# stm32f103.net
KiCad netlist of a schematic drawn in Altium Designer
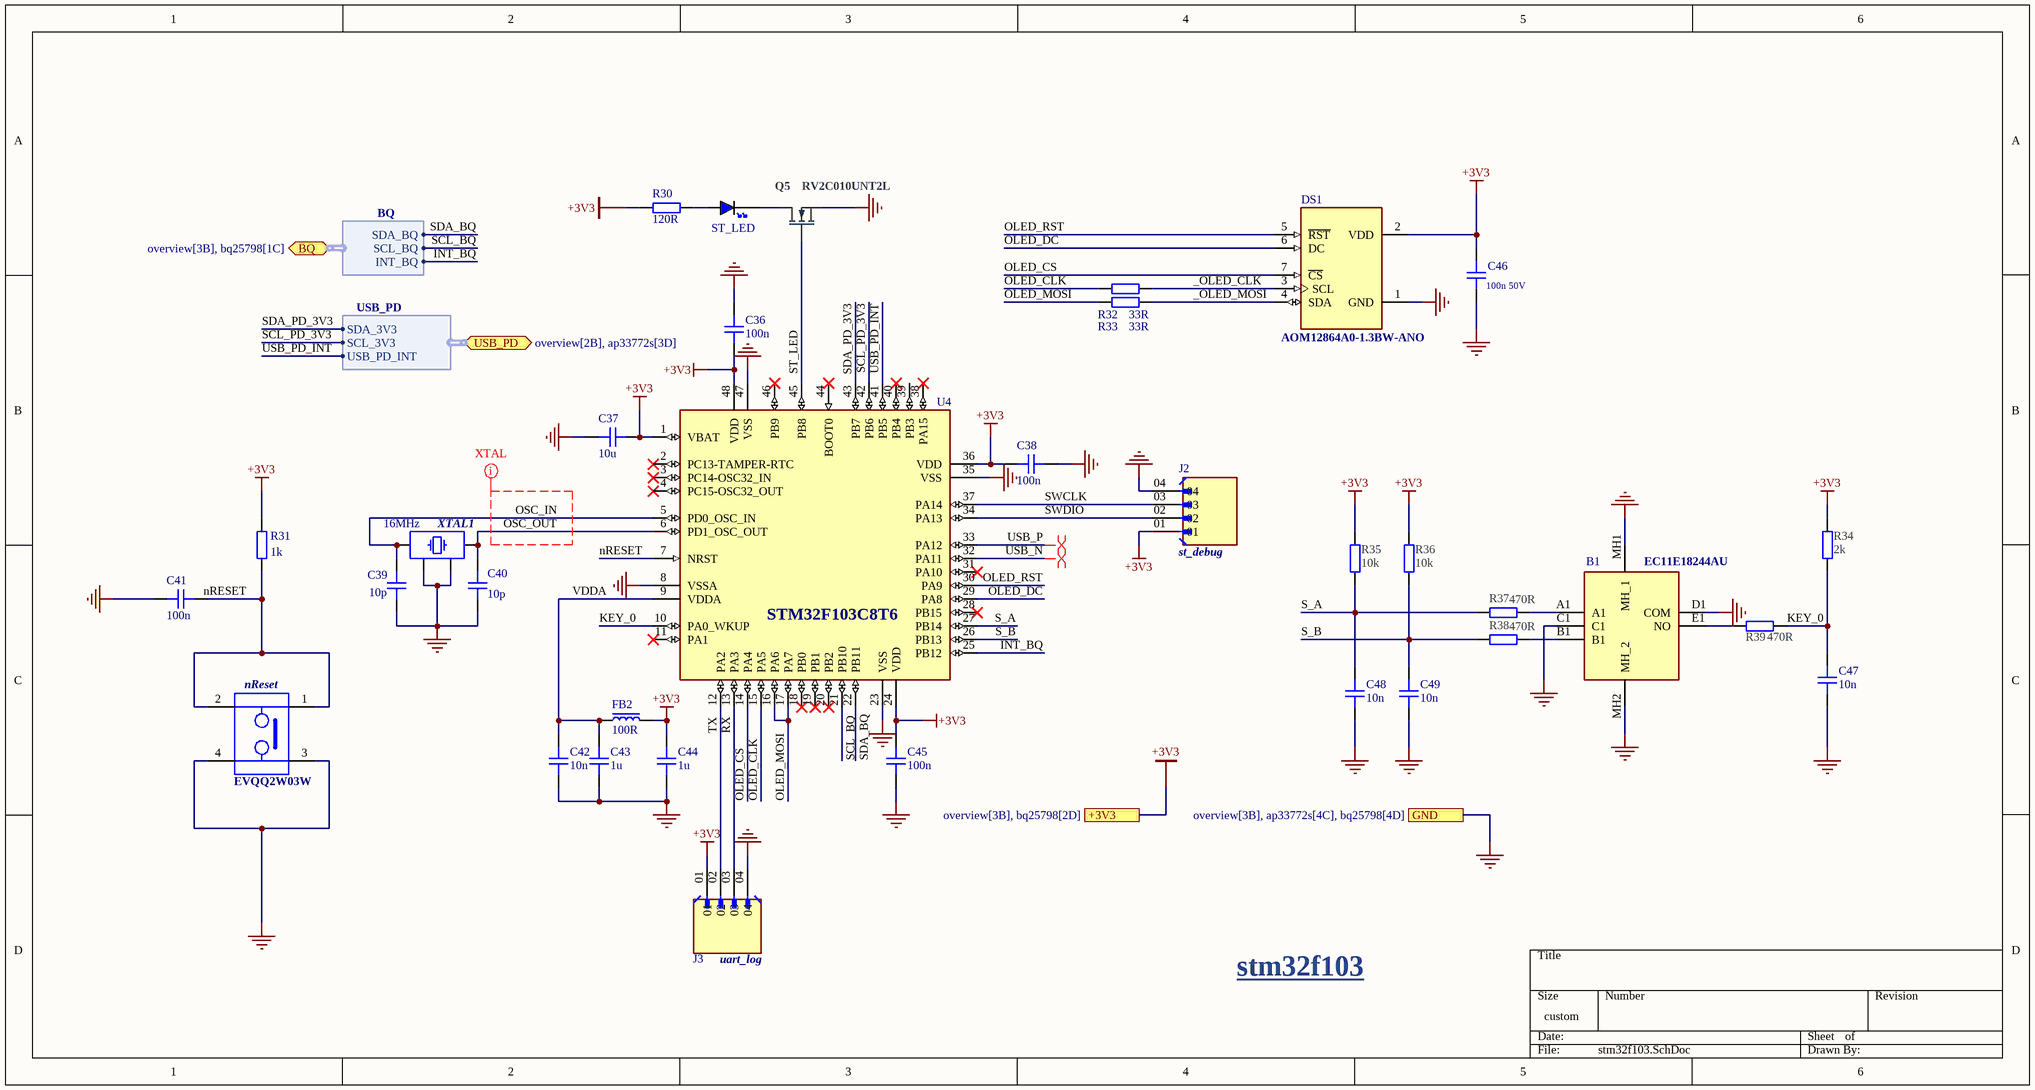
[diagram p0: stm32f103.SchDoc]

(export (version "E")
  (design (tool "Eeschema 10.0.6"))
  (components
    (comp (ref "B1")
      (value "EC11E18244AU")
      (footprint "EC11E18244AU")
      (fields (field (name "MOUSER PART NUMBER") "688-EC11E18244AU"))
      (libsource (lib "Sch_Lib") (part "EC11E18244AU"))
    )
    (comp (ref "C36")
      (value "100n")
      (footprint "CAP_0402")
      (description "Capacitor SMD 0402")
      (libsource (lib "Sch_Lib") (part "CAP_0402"))
    )
    (comp (ref "C37")
      (value "10u")
      (footprint "CAP_0402")
      (description "Capacitor SMD 0402")
      (libsource (lib "Sch_Lib") (part "CAP_0402"))
    )
    (comp (ref "C38")
      (value "100n")
      (footprint "CAP_0402")
      (description "Capacitor SMD 0402")
      (libsource (lib "Sch_Lib") (part "CAP_0402"))
    )
    (comp (ref "C39")
      (value "10p")
      (footprint "CAP_0402")
      (description "Capacitor SMD 0402")
      (libsource (lib "Schematic-Lib-PhilsLab") (part "CAP_0402"))
    )
    (comp (ref "C40")
      (value "10p")
      (footprint "CAP_0402")
      (description "Capacitor SMD 0402")
      (libsource (lib "Schematic-Lib-PhilsLab") (part "CAP_0402"))
    )
    (comp (ref "C41")
      (value "100n")
      (footprint "CAP_0603")
      (description "Capacitor SMD 0603")
      (libsource (lib "Sch_Lib") (part "CAP_0603"))
    )
    (comp (ref "C42")
      (value "10n")
      (footprint "CAP_0603")
      (description "Capacitor SMD 0603")
      (libsource (lib "Schematic-Lib-PhilsLab") (part "CAP_0603"))
    )
    (comp (ref "C43")
      (value "1u")
      (footprint "CAP_0603")
      (description "Capacitor SMD 0603")
      (libsource (lib "Schematic-Lib-PhilsLab") (part "CAP_0603"))
    )
    (comp (ref "C44")
      (value "1u")
      (footprint "CAP_0603")
      (description "Capacitor SMD 0603")
      (libsource (lib "Schematic-Lib-PhilsLab") (part "CAP_0603"))
    )
    (comp (ref "C45")
      (value "100n")
      (footprint "CAP_0402")
      (description "Capacitor SMD 0402")
      (libsource (lib "Sch_Lib") (part "CAP_0402"))
    )
    (comp (ref "C46")
      (value "100n 50V")
      (footprint "CAP_0603")
      (description "Capacitor SMD 0603")
      (libsource (lib "Sch_Lib") (part "CAP_0603"))
    )
    (comp (ref "C47")
      (value "10n")
      (footprint "CAP_0402")
      (description "Capacitor SMD 0402")
      (libsource (lib "Sch_Lib") (part "CAP_0402"))
    )
    (comp (ref "C48")
      (value "10n")
      (footprint "CAP_0402")
      (description "Capacitor SMD 0402")
      (libsource (lib "Sch_Lib") (part "CAP_0402"))
    )
    (comp (ref "C49")
      (value "10n")
      (footprint "CAP_0402")
      (description "Capacitor SMD 0402")
      (libsource (lib "Sch_Lib") (part "CAP_0402"))
    )
    (comp (ref "DS1")
      (value "AOM12864A0-1.3BW-ANO")
      (footprint "LCD_AOM12864A0-1.3BW-ANO")
      (description "Non-Touch Graphic LCD Display Module - Blue OLED SPI 1.3 (33.02mm) 128 x 64")
      (fields (field (name "MF") "Orient Display"))
      (libsource (lib "Sch_Lib") (part "AOM12864A0-1.3BW-ANO"))
    )
    (comp (ref "FB2")
      (value "100R")
      (footprint "FB_0603")
      (description "Ferrite Bead SMD 0603")
      (libsource (lib "Schematic-Lib-PhilsLab") (part "FB_0603"))
    )
    (comp (ref "J2")
      (value "st_debug")
      (footprint "SAMTEC_TSW-104-08-T-S-LL")
      (fields (field (name "MF") "Samtec") (field (name "MP") "TSW-104-08-T-S-LL"))
      (libsource (lib "Sch_Lib") (part "4PIN_TSW-104-08-T-S-LL"))
    )
    (comp (ref "J3")
      (value "uart_log")
      (footprint "SAMTEC_TSW-104-08-T-S-LL")
      (fields (field (name "MF") "Samtec") (field (name "MP") "TSW-104-08-T-S-LL"))
      (libsource (lib "") (part "4PIN_TSW-104-08-T-S-LL_1"))
    )
    (comp (ref "nReset")
      (value "EVQQ2W03W")
      (footprint "EVQQ2W03W")
      (description "White Push Plate Tactile Switch, SPST-NO 20 mA 3.1mm")
      (fields (field (name "MF") "Panasonic"))
      (libsource (lib "Sch_Lib") (part "EVQQ2W03W"))
    )
    (comp (ref "Q5")
      (value "RV2C010UNT2L")
      (footprint "DFN65P100X40-3L")
      (description "N-Channel MOSFET, 20V, 1A, 470mOhm, 400mW")
      (fields (field (name "MANUFACTURER") "Rohm Semiconductor") (field (name "AUTHOR") "rsk"))
      (libsource (lib "Sch_Lib") (part "RV2C010UNT2L"))
    )
    (comp (ref "R30")
      (value "120R")
      (footprint "RES_0603")
      (description "Resistor SMD 0603")
      (libsource (lib "Schematic-Lib-PhilsLab") (part "RES_0603"))
    )
    (comp (ref "R31")
      (value "1k")
      (footprint "RES_0603")
      (description "Resistor SMD 0603")
      (libsource (lib "Schematic-Lib-PhilsLab") (part "RES_0603"))
    )
    (comp (ref "R32")
      (value "33R")
      (footprint "RES_0603")
      (description "Resistor SMD 0603")
      (libsource (lib "Sch_Lib") (part "RES_0603"))
    )
    (comp (ref "R33")
      (value "33R")
      (footprint "RES_0603")
      (description "Resistor SMD 0603")
      (libsource (lib "Sch_Lib") (part "RES_0603"))
    )
    (comp (ref "R34")
      (value "2k")
      (footprint "RESC1005X04L")
      (description "Resistor, ±5%, 0.063W")
      (fields
        (field (name "PART NUMBER") "R0402-0R")
        (field (name "MANUFACTURER") "N.A.")
        (field (name "AUTHOR") "rsk")
      )
      (libsource (lib "Sch_Lib") (part "R0402-0R"))
    )
    (comp (ref "R35")
      (value "10k")
      (footprint "RESC1005X04L")
      (description "Resistor, ±5%, 0.063W")
      (fields
        (field (name "PART NUMBER") "R0402-0R")
        (field (name "MANUFACTURER") "N.A.")
        (field (name "AUTHOR") "rsk")
      )
      (libsource (lib "Sch_Lib") (part "R0402-0R"))
    )
    (comp (ref "R36")
      (value "10k")
      (footprint "RESC1005X04L")
      (description "Resistor, ±5%, 0.063W")
      (fields
        (field (name "PART NUMBER") "R0402-0R")
        (field (name "MANUFACTURER") "N.A.")
        (field (name "AUTHOR") "rsk")
      )
      (libsource (lib "Sch_Lib") (part "R0402-0R"))
    )
    (comp (ref "R37")
      (value "470R")
      (footprint "RESC1005X04L")
      (description "Resistor, ±5%, 0.063W")
      (fields
        (field (name "PART NUMBER") "R0402-0R")
        (field (name "MANUFACTURER") "N.A.")
        (field (name "AUTHOR") "rsk")
      )
      (libsource (lib "Sch_Lib") (part "R0402-0R"))
    )
    (comp (ref "R38")
      (value "470R")
      (footprint "RESC1005X04L")
      (description "Resistor, ±5%, 0.063W")
      (fields
        (field (name "PART NUMBER") "R0402-0R")
        (field (name "MANUFACTURER") "N.A.")
        (field (name "AUTHOR") "rsk")
      )
      (libsource (lib "Sch_Lib") (part "R0402-0R"))
    )
    (comp (ref "R39")
      (value "470R")
      (footprint "RESC1005X04L")
      (description "Resistor, ±5%, 0.063W")
      (fields
        (field (name "PART NUMBER") "R0402-0R")
        (field (name "MANUFACTURER") "N.A.")
        (field (name "AUTHOR") "rsk")
      )
      (libsource (lib "Sch_Lib") (part "R0402-0R"))
    )
    (comp (ref "ST_LED")
      (value "BLUE")
      (footprint "LED_0603_BLUE")
      (description "LED 0603 BLUE SMD")
      (libsource (lib "Sch_Lib") (part "LED_0603_BLUE"))
    )
    (comp (ref "U4")
      (value "STM32F103C8T6")
      (footprint "QFP50P900X900X160-48N")
      (description "ARMÂ® CortexÂ®-M3 STM32F1 Microcontroller IC 32-Bit 72MHz 64KB (64K x 8) FLASH 48-LQFP (7x7)")
      (fields (field (name "MF") "STMicroelectronics"))
      (libsource (lib "Sch_Lib") (part "STM32F103C8T6"))
    )
    (comp (ref "XTAL1")
      (value "16MHz")
      (footprint "XTAL_2520")
      (description "Crystal SMD 2520")
      (libsource (lib "Schematic-Lib-PhilsLab") (part "XTAL_2520"))
    )
  )
  (nets
    (net (code "3") (name "+3V3") (class "Default")
      (node (ref "C36") (pin "2") (pinfunction "2_2") (pintype "passive"))
      (node (ref "C37") (pin "2") (pinfunction "2_2") (pintype "passive"))
      (node (ref "C38") (pin "1") (pinfunction "1_1") (pintype "passive"))
      (node (ref "C44") (pin "2") (pinfunction "2_2") (pintype "passive"))
      (node (ref "C45") (pin "2") (pinfunction "2_2") (pintype "passive"))
      (node (ref "C46") (pin "2") (pinfunction "2_2") (pintype "passive"))
      (node (ref "DS1") (pin "2") (pinfunction "VDD_2") (pintype "power_in"))
      (node (ref "FB2") (pin "2") (pinfunction "2_2") (pintype "passive"))
      (node (ref "J2") (pin "01") (pinfunction "01_01") (pintype "passive"))
      (node (ref "J3") (pin "01") (pinfunction "01_01") (pintype "passive"))
      (node (ref "R30") (pin "2") (pinfunction "2_2") (pintype "passive"))
      (node (ref "R31") (pin "1") (pinfunction "1_1") (pintype "passive"))
      (node (ref "R34") (pin "2") (pinfunction "2_2") (pintype "passive"))
      (node (ref "R35") (pin "2") (pinfunction "2_2") (pintype "passive"))
      (node (ref "R36") (pin "2") (pinfunction "2_2") (pintype "passive"))
      (node (ref "U4") (pin "1") (pinfunction "VBAT_1") (pintype "bidirectional"))
      (node (ref "U4") (pin "24") (pinfunction "VDD_24") (pintype "power_in"))
      (node (ref "U4") (pin "36") (pinfunction "VDD_36") (pintype "power_in"))
      (node (ref "U4") (pin "48") (pinfunction "VDD_48") (pintype "power_in"))
    )
    (net (code "4") (name "/INT_BQ") (class "Default")
      (node (ref "U4") (pin "25") (pinfunction "PB12_25") (pintype "bidirectional"))
    )
    (net (code "5") (name "/KEY_0") (class "Default")
      (node (ref "C47") (pin "2") (pinfunction "2_2") (pintype "passive"))
      (node (ref "R34") (pin "1") (pinfunction "1_1") (pintype "passive"))
      (node (ref "R39") (pin "2") (pinfunction "2_2") (pintype "passive"))
      (node (ref "U4") (pin "10") (pinfunction "PA0_WKUP_10") (pintype "bidirectional"))
    )
    (net (code "6") (name "/OLED_CLK") (class "Default")
      (node (ref "R32") (pin "1") (pinfunction "1_1") (pintype "passive"))
      (node (ref "U4") (pin "15") (pinfunction "PA5_15") (pintype "bidirectional"))
    )
    (net (code "7") (name "/OLED_CS") (class "Default")
      (node (ref "DS1") (pin "7") (pinfunction "~{CS}_7") (pintype "input"))
      (node (ref "U4") (pin "14") (pinfunction "PA4_14") (pintype "bidirectional"))
    )
    (net (code "8") (name "/OLED_DC") (class "Default")
      (node (ref "DS1") (pin "6") (pinfunction "DC_6") (pintype "input"))
      (node (ref "U4") (pin "29") (pinfunction "PA8_29") (pintype "bidirectional"))
    )
    (net (code "9") (name "/OLED_MOSI") (class "Default")
      (node (ref "R33") (pin "1") (pinfunction "1_1") (pintype "passive"))
      (node (ref "U4") (pin "16") (pinfunction "PA6_16") (pintype "bidirectional"))
      (node (ref "U4") (pin "17") (pinfunction "PA7_17") (pintype "bidirectional"))
    )
    (net (code "10") (name "/OLED_RST") (class "Default")
      (node (ref "DS1") (pin "5") (pinfunction "~{RST}_5") (pintype "input"))
      (node (ref "U4") (pin "30") (pinfunction "PA9_30") (pintype "bidirectional"))
    )
    (net (code "11") (name "/OSC_IN") (class "Default")
      (node (ref "C39") (pin "2") (pinfunction "2_2") (pintype "passive"))
      (node (ref "U4") (pin "5") (pinfunction "PD0_OSC_IN_5") (pintype "bidirectional"))
      (node (ref "XTAL1") (pin "3") (pinfunction "3_3") (pintype "passive"))
    )
    (net (code "12") (name "/OSC_OUT") (class "Default")
      (node (ref "C40") (pin "2") (pinfunction "2_2") (pintype "passive"))
      (node (ref "U4") (pin "6") (pinfunction "PD1_OSC_OUT_6") (pintype "bidirectional"))
      (node (ref "XTAL1") (pin "1") (pinfunction "1_1") (pintype "passive"))
    )
    (net (code "13") (name "/RX") (class "Default")
      (node (ref "J3") (pin "03") (pinfunction "03_03") (pintype "passive"))
      (node (ref "U4") (pin "13") (pinfunction "PA3_13") (pintype "bidirectional"))
    )
    (net (code "14") (name "/SCL_BQ") (class "Default")
      (node (ref "U4") (pin "21") (pinfunction "PB10_21") (pintype "bidirectional"))
    )
    (net (code "15") (name "/SCL_PD_3V3") (class "Default")
      (node (ref "U4") (pin "42") (pinfunction "PB6_42") (pintype "bidirectional"))
    )
    (net (code "16") (name "/SDA_BQ") (class "Default")
      (node (ref "U4") (pin "22") (pinfunction "PB11_22") (pintype "bidirectional"))
    )
    (net (code "17") (name "/SDA_PD_3V3") (class "Default")
      (node (ref "U4") (pin "43") (pinfunction "PB7_43") (pintype "bidirectional"))
    )
    (net (code "18") (name "/ST_LED") (class "Default")
      (node (ref "Q5") (pin "1") (pinfunction "G_1") (pintype "passive"))
      (node (ref "U4") (pin "45") (pinfunction "PB8_45") (pintype "bidirectional"))
    )
    (net (code "19") (name "/SWCLK") (class "Default")
      (node (ref "J2") (pin "03") (pinfunction "03_03") (pintype "passive"))
      (node (ref "U4") (pin "37") (pinfunction "PA14_37") (pintype "bidirectional"))
    )
    (net (code "20") (name "/SWDIO") (class "Default")
      (node (ref "J2") (pin "02") (pinfunction "02_02") (pintype "passive"))
      (node (ref "U4") (pin "34") (pinfunction "PA13_34") (pintype "bidirectional"))
    )
    (net (code "21") (name "/S_A") (class "Default")
      (node (ref "C48") (pin "2") (pinfunction "2_2") (pintype "passive"))
      (node (ref "R35") (pin "1") (pinfunction "1_1") (pintype "passive"))
      (node (ref "R37") (pin "1") (pinfunction "1_1") (pintype "passive"))
      (node (ref "U4") (pin "27") (pinfunction "PB14_27") (pintype "bidirectional"))
    )
    (net (code "22") (name "/S_B") (class "Default")
      (node (ref "C49") (pin "2") (pinfunction "2_2") (pintype "passive"))
      (node (ref "R36") (pin "1") (pinfunction "1_1") (pintype "passive"))
      (node (ref "R38") (pin "1") (pinfunction "1_1") (pintype "passive"))
      (node (ref "U4") (pin "26") (pinfunction "PB13_26") (pintype "bidirectional"))
    )
    (net (code "23") (name "/TX") (class "Default")
      (node (ref "J3") (pin "02") (pinfunction "02_02") (pintype "passive"))
      (node (ref "U4") (pin "12") (pinfunction "PA2_12") (pintype "bidirectional"))
    )
    (net (code "24") (name "/USB_N") (class "Default")
      (node (ref "U4") (pin "32") (pinfunction "PA11_32") (pintype "bidirectional"))
    )
    (net (code "25") (name "/USB_P") (class "Default")
      (node (ref "U4") (pin "33") (pinfunction "PA12_33") (pintype "bidirectional"))
    )
    (net (code "26") (name "/USB_PD_INT") (class "Default")
      (node (ref "U4") (pin "41") (pinfunction "PB5_41") (pintype "bidirectional"))
    )
    (net (code "27") (name "/VDDA") (class "Default")
      (node (ref "C42") (pin "2") (pinfunction "2_2") (pintype "passive"))
      (node (ref "C43") (pin "2") (pinfunction "2_2") (pintype "passive"))
      (node (ref "FB2") (pin "1") (pinfunction "1_1") (pintype "passive"))
      (node (ref "U4") (pin "9") (pinfunction "VDDA_9") (pintype "power_in"))
    )
    (net (code "28") (name "/_OLED_CLK") (class "Default")
      (node (ref "DS1") (pin "3") (pinfunction "SCL_3") (pintype "input"))
      (node (ref "R32") (pin "2") (pinfunction "2_2") (pintype "passive"))
    )
    (net (code "29") (name "/_OLED_MOSI") (class "Default")
      (node (ref "DS1") (pin "4") (pinfunction "SDA_4") (pintype "bidirectional"))
      (node (ref "R33") (pin "2") (pinfunction "2_2") (pintype "passive"))
    )
    (net (code "30") (name "/nRESET") (class "Default")
      (node (ref "C41") (pin "2") (pinfunction "2_2") (pintype "passive"))
      (node (ref "R31") (pin "2") (pinfunction "2_2") (pintype "passive"))
      (node (ref "U4") (pin "7") (pinfunction "NRST_7") (pintype "input"))
      (node (ref "nReset") (pin "1") (pinfunction "1_1") (pintype "passive"))
      (node (ref "nReset") (pin "2") (pinfunction "2_2") (pintype "passive"))
    )
    (net (code "33") (name "GND") (class "Default")
      (node (ref "B1") (pin "C1") (pinfunction "C1_C1") (pintype "passive"))
      (node (ref "B1") (pin "D1") (pinfunction "COM_D1") (pintype "passive"))
      (node (ref "B1") (pin "MH1") (pinfunction "MH_1_MH1") (pintype "passive"))
      (node (ref "B1") (pin "MH2") (pinfunction "MH_2_MH2") (pintype "passive"))
      (node (ref "C36") (pin "1") (pinfunction "1_1") (pintype "passive"))
      (node (ref "C37") (pin "1") (pinfunction "1_1") (pintype "passive"))
      (node (ref "C38") (pin "2") (pinfunction "2_2") (pintype "passive"))
      (node (ref "C39") (pin "1") (pinfunction "1_1") (pintype "passive"))
      (node (ref "C40") (pin "1") (pinfunction "1_1") (pintype "passive"))
      (node (ref "C41") (pin "1") (pinfunction "1_1") (pintype "passive"))
      (node (ref "C42") (pin "1") (pinfunction "1_1") (pintype "passive"))
      (node (ref "C43") (pin "1") (pinfunction "1_1") (pintype "passive"))
      (node (ref "C44") (pin "1") (pinfunction "1_1") (pintype "passive"))
      (node (ref "C45") (pin "1") (pinfunction "1_1") (pintype "passive"))
      (node (ref "C46") (pin "1") (pinfunction "1_1") (pintype "passive"))
      (node (ref "C47") (pin "1") (pinfunction "1_1") (pintype "passive"))
      (node (ref "C48") (pin "1") (pinfunction "1_1") (pintype "passive"))
      (node (ref "C49") (pin "1") (pinfunction "1_1") (pintype "passive"))
      (node (ref "DS1") (pin "1") (pinfunction "GND_1") (pintype "power_in"))
      (node (ref "J2") (pin "04") (pinfunction "04_04") (pintype "passive"))
      (node (ref "J3") (pin "04") (pinfunction "04_04") (pintype "passive"))
      (node (ref "Q5") (pin "2") (pinfunction "S_2") (pintype "passive"))
      (node (ref "U4") (pin "23") (pinfunction "VSS_23") (pintype "power_in"))
      (node (ref "U4") (pin "35") (pinfunction "VSS_35") (pintype "power_in"))
      (node (ref "U4") (pin "47") (pinfunction "VSS_47") (pintype "power_in"))
      (node (ref "U4") (pin "8") (pinfunction "VSSA_8") (pintype "power_in"))
      (node (ref "XTAL1") (pin "2") (pinfunction "2_2") (pintype "passive"))
      (node (ref "XTAL1") (pin "4") (pinfunction "4_4") (pintype "passive"))
      (node (ref "nReset") (pin "3") (pinfunction "3_3") (pintype "passive"))
      (node (ref "nReset") (pin "4") (pinfunction "4_4") (pintype "passive"))
    )
    (net (code "34") (name "Net-(B1-NO)") (class "Default")
      (node (ref "B1") (pin "E1") (pinfunction "NO_E1") (pintype "passive"))
      (node (ref "R39") (pin "1") (pinfunction "1_1") (pintype "passive"))
    )
    (net (code "35") (name "Net-(B1-PadA1)") (class "Default")
      (node (ref "B1") (pin "A1") (pinfunction "A1_A1") (pintype "passive"))
      (node (ref "R37") (pin "2") (pinfunction "2_2") (pintype "passive"))
    )
    (net (code "36") (name "Net-(B1-PadB1)") (class "Default")
      (node (ref "B1") (pin "B1") (pinfunction "B1_B1") (pintype "passive"))
      (node (ref "R38") (pin "2") (pinfunction "2_2") (pintype "passive"))
    )
    (net (code "37") (name "Net-(Q5-D)") (class "Default")
      (node (ref "Q5") (pin "3") (pinfunction "D_3") (pintype "passive"))
      (node (ref "ST_LED") (pin "K") (pinfunction "K_K") (pintype "passive"))
    )
    (net (code "38") (name "Net-(R30-Pad1)") (class "Default")
      (node (ref "R30") (pin "1") (pinfunction "1_1") (pintype "passive"))
      (node (ref "ST_LED") (pin "A") (pinfunction "A_A") (pintype "passive"))
    )
    (net (code "39") (name "unconnected-(U4-BOOT0-Pad44)") (class "Default")
      (node (ref "U4") (pin "44") (pinfunction "BOOT0_44") (pintype "input+no_connect"))
    )
    (net (code "40") (name "unconnected-(U4-PA1-Pad11)") (class "Default")
      (node (ref "U4") (pin "11") (pinfunction "PA1_11") (pintype "bidirectional+no_connect"))
    )
    (net (code "41") (name "unconnected-(U4-PA10-Pad31)") (class "Default")
      (node (ref "U4") (pin "31") (pinfunction "PA10_31") (pintype "bidirectional+no_connect"))
    )
    (net (code "42") (name "unconnected-(U4-PA15-Pad38)") (class "Default")
      (node (ref "U4") (pin "38") (pinfunction "PA15_38") (pintype "bidirectional+no_connect"))
    )
    (net (code "43") (name "unconnected-(U4-PB0-Pad18)") (class "Default")
      (node (ref "U4") (pin "18") (pinfunction "PB0_18") (pintype "bidirectional+no_connect"))
    )
    (net (code "44") (name "unconnected-(U4-PB1-Pad19)") (class "Default")
      (node (ref "U4") (pin "19") (pinfunction "PB1_19") (pintype "bidirectional+no_connect"))
    )
    (net (code "45") (name "unconnected-(U4-PB2-Pad20)") (class "Default")
      (node (ref "U4") (pin "20") (pinfunction "PB2_20") (pintype "bidirectional+no_connect"))
    )
    (net (code "46") (name "unconnected-(U4-PB3-Pad39)") (class "Default")
      (node (ref "U4") (pin "39") (pinfunction "PB3_39") (pintype "bidirectional"))
    )
    (net (code "47") (name "unconnected-(U4-PB4-Pad40)") (class "Default")
      (node (ref "U4") (pin "40") (pinfunction "PB4_40") (pintype "bidirectional+no_connect"))
    )
    (net (code "48") (name "unconnected-(U4-PB9-Pad46)") (class "Default")
      (node (ref "U4") (pin "46") (pinfunction "PB9_46") (pintype "bidirectional+no_connect"))
    )
    (net (code "49") (name "unconnected-(U4-PB15-Pad28)") (class "Default")
      (node (ref "U4") (pin "28") (pinfunction "PB15_28") (pintype "bidirectional+no_connect"))
    )
    (net (code "50") (name "unconnected-(U4-PC13-TAMPER-RTC-Pad2)") (class "Default")
      (node (ref "U4") (pin "2") (pinfunction "PC13-TAMPER-RTC_2") (pintype "bidirectional+no_connect"))
    )
    (net (code "51") (name "unconnected-(U4-PC14-OSC32_IN-Pad3)") (class "Default")
      (node (ref "U4") (pin "3") (pinfunction "PC14-OSC32_IN_3") (pintype "bidirectional+no_connect"))
    )
    (net (code "52") (name "unconnected-(U4-PC15-OSC32_OUT-Pad4)") (class "Default")
      (node (ref "U4") (pin "4") (pinfunction "PC15-OSC32_OUT_4") (pintype "bidirectional+no_connect"))
    )
  )
)
